# MCU.net
KiCad netlist of a schematic drawn in Altium Designer
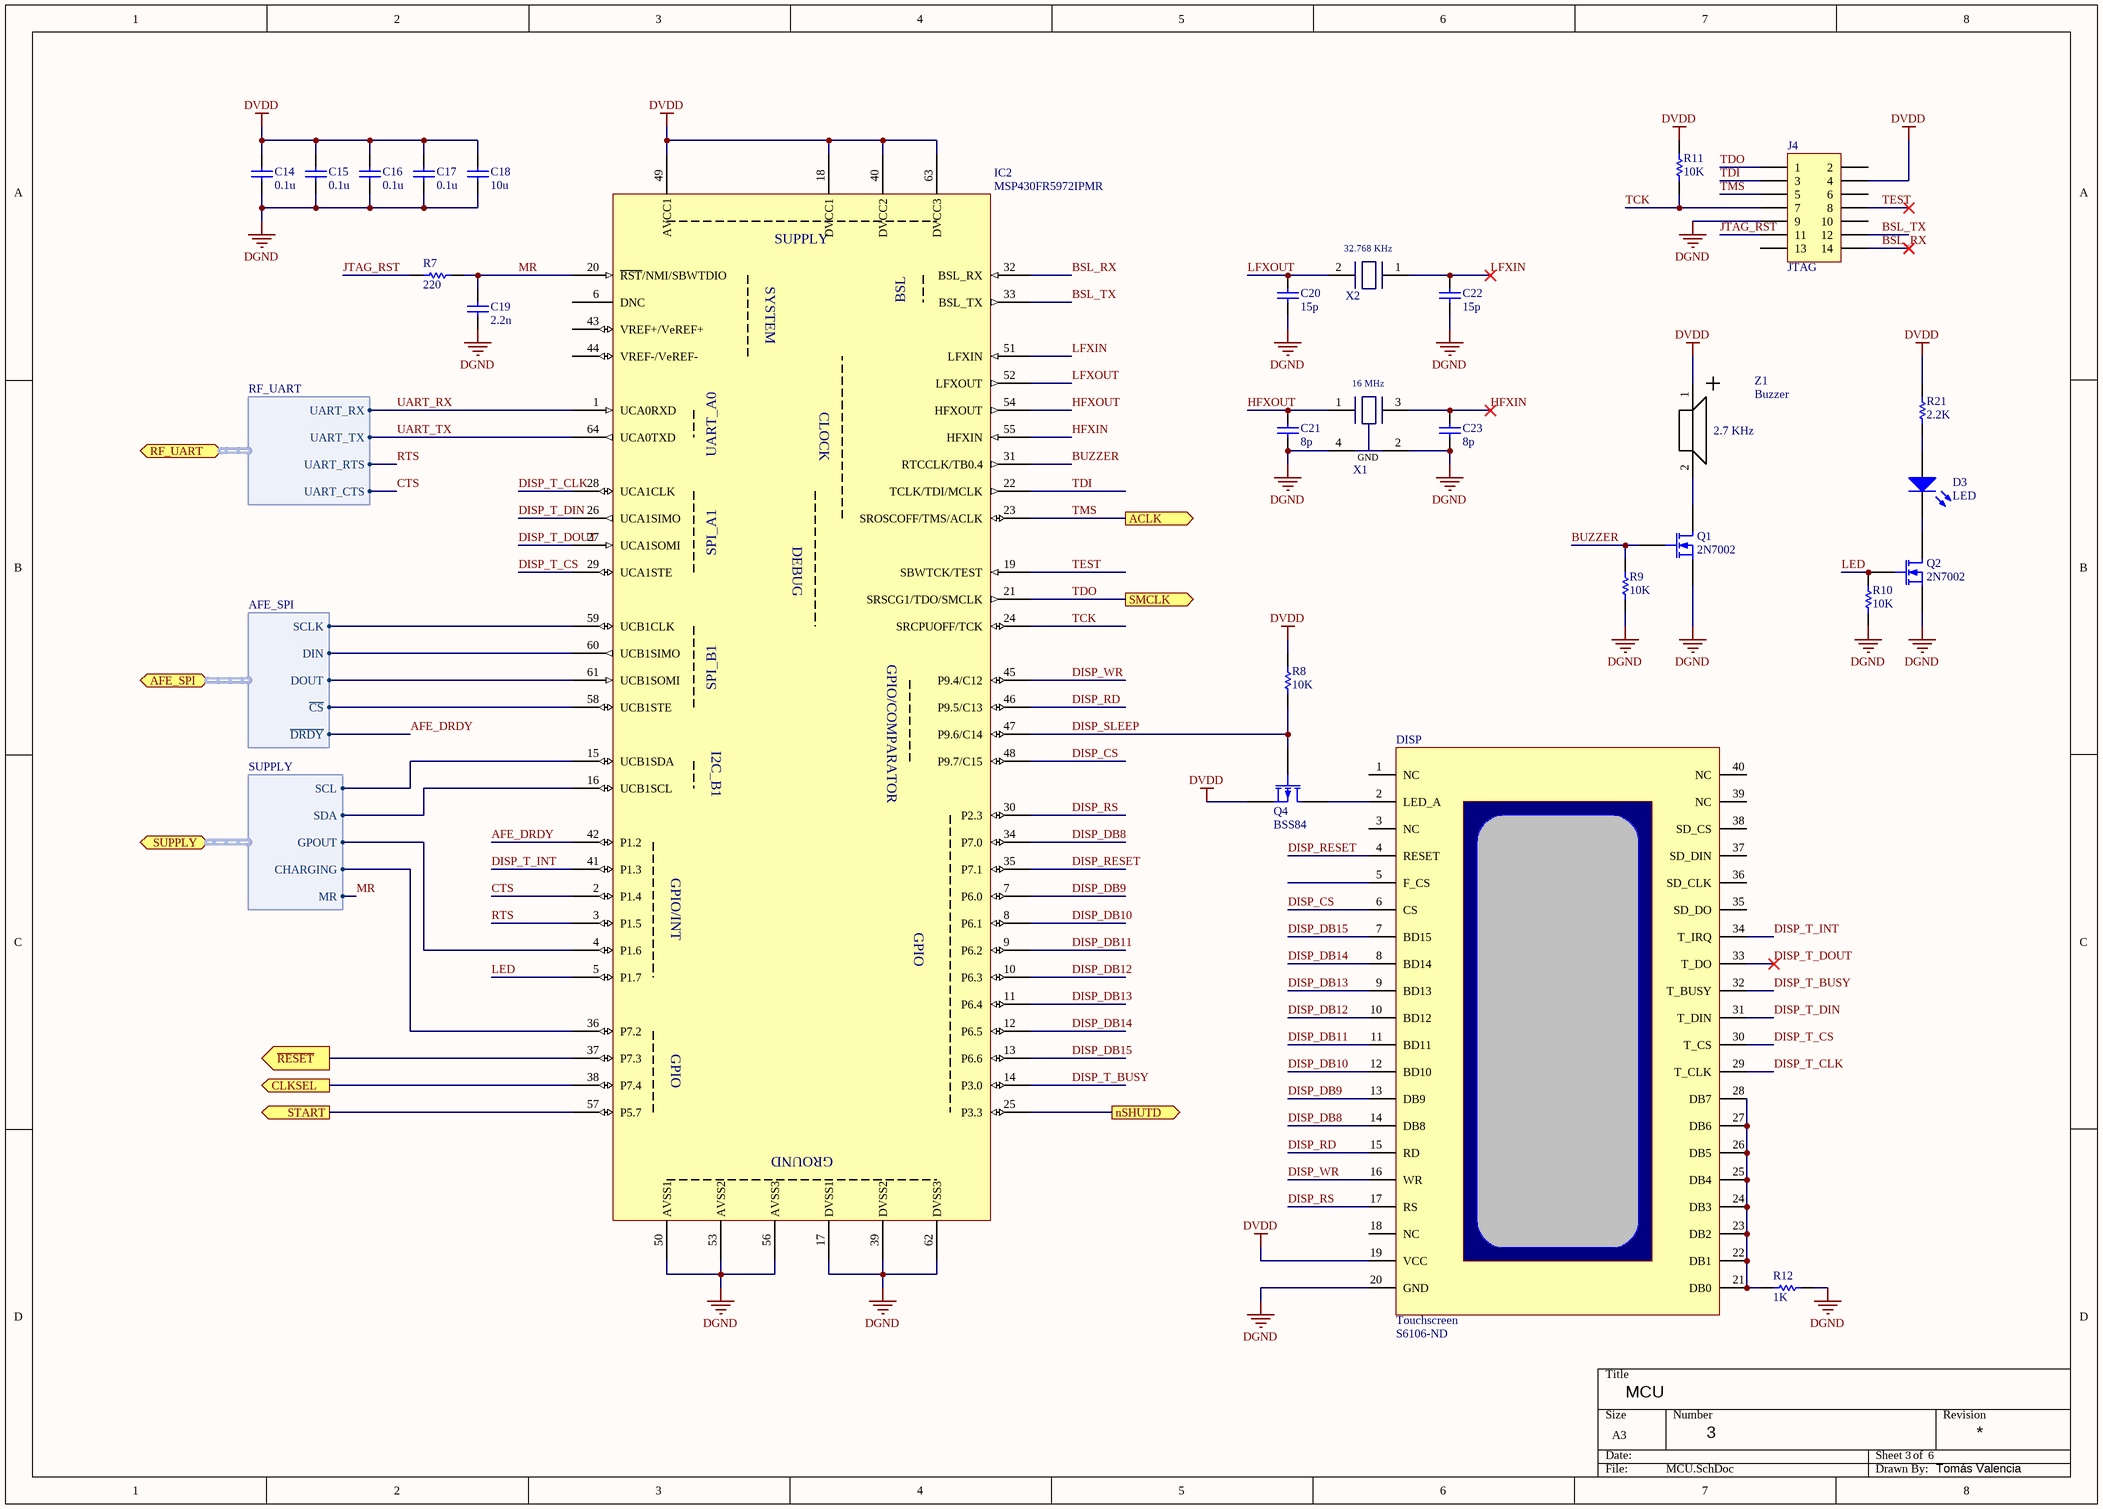
[diagram p0: MCU.SchDoc]

(export (version "E")
  (design (tool "Eeschema 10.0.6"))
  (components
    (comp (ref "C14")
      (value "0.1u")
      (footprint "C0603")
      (description "Capacitor")
      (libsource (lib "Common Devices") (part "Capacitor"))
    )
    (comp (ref "C15")
      (value "0.1u")
      (footprint "C0603")
      (description "Capacitor")
      (libsource (lib "Common Devices") (part "Capacitor"))
    )
    (comp (ref "C16")
      (value "0.1u")
      (footprint "C0603")
      (description "Capacitor")
      (libsource (lib "Common Devices") (part "Capacitor"))
    )
    (comp (ref "C17")
      (value "0.1u")
      (footprint "C0603")
      (description "Capacitor")
      (libsource (lib "Common Devices") (part "Capacitor"))
    )
    (comp (ref "C18")
      (value "10u")
      (footprint "C0603")
      (description "Capacitor")
      (libsource (lib "Common Devices") (part "Capacitor"))
    )
    (comp (ref "C19")
      (value "2.2n")
      (footprint "C0603")
      (description "Capacitor")
      (libsource (lib "Common Devices") (part "Capacitor"))
    )
    (comp (ref "C20")
      (value "15p")
      (footprint "C0603")
      (description "Capacitor")
      (libsource (lib "Common Devices") (part "Capacitor"))
    )
    (comp (ref "C21")
      (value "8p")
      (footprint "C0603")
      (description "Capacitor")
      (libsource (lib "Common Devices") (part "Capacitor"))
    )
    (comp (ref "C22")
      (value "15p")
      (footprint "C0603")
      (description "Capacitor")
      (libsource (lib "Common Devices") (part "Capacitor"))
    )
    (comp (ref "C23")
      (value "8p")
      (footprint "C0603")
      (description "Capacitor")
      (libsource (lib "Common Devices") (part "Capacitor"))
    )
    (comp (ref "D3") (value "LED") (footprint "LED3015M") (libsource (lib "Common Devices") (part "LED")))
    (comp (ref "DISP")
      (value "Touchscreen")
      (footprint "TSCREEN_CONN")
      (fields (field (name "SUPPLIER PART NUMBER 1") "S6106-ND"))
      (libsource (lib "Main Board") (part "Touchscreen"))
    )
    (comp (ref "IC2")
      (value "MSP430FR5972IPMR")
      (footprint "MSP430FR5972")
      (libsource (lib "Main Board") (part "MSP430FR5972IPMR"))
    )
    (comp (ref "J4")
      (value "JTAG")
      (footprint "JTAG 14 PINS")
      (description "JTAG 7X2 Pin Header 90º")
      (libsource (lib "Main Board") (part "JTAG 14 Pins"))
    )
    (comp (ref "Q1")
      (value "2N7002")
      (footprint "SOT65P210X110-3N")
      (description "Transistor, MOSFET, N-Channel, 60V, 300mA")
      (libsource (lib "Common Devices") (part "2N7002"))
    )
    (comp (ref "Q2")
      (value "2N7002")
      (footprint "SOT65P210X110-3N")
      (description "Transistor, MOSFET, N-Channel, 60V, 300mA")
      (libsource (lib "Common Devices") (part "2N7002"))
    )
    (comp (ref "Q4")
      (value "BSS84")
      (footprint "SOT65P210X110-3N")
      (description "Transistor, MOSFET, P-Channel, 60V, 300mA")
      (libsource (lib "Common Devices") (part "BSS84"))
    )
    (comp (ref "R7")
      (value "220")
      (footprint "R0603")
      (description "Resistor")
      (libsource (lib "Common Devices") (part "Resistor"))
    )
    (comp (ref "R8")
      (value "10K")
      (footprint "R0603")
      (description "Resistor")
      (libsource (lib "Common Devices") (part "Resistor"))
    )
    (comp (ref "R9")
      (value "10K")
      (footprint "R0603")
      (description "Resistor")
      (libsource (lib "Common Devices") (part "Resistor"))
    )
    (comp (ref "R10")
      (value "10K")
      (footprint "R0603")
      (description "Resistor")
      (libsource (lib "Common Devices") (part "Resistor"))
    )
    (comp (ref "R11")
      (value "10K")
      (footprint "R0603")
      (description "Resistor")
      (libsource (lib "Common Devices") (part "Resistor"))
    )
    (comp (ref "R12")
      (value "1K")
      (footprint "R0603")
      (description "Resistor")
      (libsource (lib "Common Devices") (part "Resistor"))
    )
    (comp (ref "R21")
      (value "2.2K")
      (footprint "R0603")
      (description "Resistor")
      (libsource (lib "Common Devices") (part "Resistor"))
    )
    (comp (ref "X1")
      (value "XTAL_16MHZ")
      (footprint "XTAL_16_MHz")
      (libsource (lib "Main Board") (part "XTAL_16_MHz"))
    )
    (comp (ref "X2")
      (value "XTAL_32768")
      (footprint "xtal_32768")
      (libsource (lib "Main Board") (part "XTAL_32768"))
    )
    (comp (ref "Z1")
      (value "Buzzer")
      (footprint "KSSG74B16")
      (description "Magnetic Buzzer 2.7 KHz")
      (libsource (lib "Main Board") (part "Buzzer"))
    )
  )
  (nets
    (net (code "4") (name "/AFE_DRDY") (class "Default")
      (node (ref "IC2") (pin "42") (pinfunction "P1.2_42") (pintype "bidirectional"))
    )
    (net (code "5") (name "/BSL_RX") (class "Default")
      (node (ref "IC2") (pin "32") (pinfunction "BSL_RX_32") (pintype "input"))
      (node (ref "J4") (pin "14") (pinfunction "14_14") (pintype "passive"))
    )
    (net (code "6") (name "/BSL_TX") (class "Default")
      (node (ref "IC2") (pin "33") (pinfunction "BSL_TX_33") (pintype "output"))
      (node (ref "J4") (pin "12") (pinfunction "12_12") (pintype "passive"))
    )
    (net (code "7") (name "/BUZZER") (class "Default")
      (node (ref "IC2") (pin "31") (pinfunction "RTCCLK/TB0.4_31") (pintype "output"))
      (node (ref "Q1") (pin "1") (pinfunction "G_1") (pintype "passive"))
      (node (ref "R9") (pin "2") (pinfunction "2_2") (pintype "passive"))
    )
    (net (code "8") (name "/CHARGING") (class "Default")
      (node (ref "IC2") (pin "36") (pinfunction "P7.2_36") (pintype "bidirectional"))
    )
    (net (code "9") (name "/CLKSEL") (class "Default")
      (node (ref "IC2") (pin "38") (pinfunction "P7.4_38") (pintype "bidirectional"))
    )
    (net (code "10") (name "/CTS") (class "Default")
      (node (ref "IC2") (pin "2") (pinfunction "P1.4_2") (pintype "bidirectional"))
    )
    (net (code "11") (name "/DIN") (class "Default")
      (node (ref "IC2") (pin "60") (pinfunction "UCB1SIMO_60") (pintype "output"))
    )
    (net (code "12") (name "/DISP_CS") (class "Default")
      (node (ref "DISP") (pin "6") (pinfunction "CS_6") (pintype "passive"))
      (node (ref "IC2") (pin "48") (pinfunction "P9.7/C15_48") (pintype "bidirectional"))
    )
    (net (code "13") (name "/DISP_DB8") (class "Default")
      (node (ref "DISP") (pin "14") (pinfunction "DB8_14") (pintype "passive"))
      (node (ref "IC2") (pin "34") (pinfunction "P7.0_34") (pintype "bidirectional"))
    )
    (net (code "14") (name "/DISP_DB9") (class "Default")
      (node (ref "DISP") (pin "13") (pinfunction "DB9_13") (pintype "passive"))
      (node (ref "IC2") (pin "7") (pinfunction "P6.0_7") (pintype "bidirectional"))
    )
    (net (code "15") (name "/DISP_DB10") (class "Default")
      (node (ref "DISP") (pin "12") (pinfunction "BD10_12") (pintype "passive"))
      (node (ref "IC2") (pin "8") (pinfunction "P6.1_8") (pintype "bidirectional"))
    )
    (net (code "16") (name "/DISP_DB11") (class "Default")
      (node (ref "DISP") (pin "11") (pinfunction "BD11_11") (pintype "passive"))
      (node (ref "IC2") (pin "9") (pinfunction "P6.2_9") (pintype "bidirectional"))
    )
    (net (code "17") (name "/DISP_DB12") (class "Default")
      (node (ref "DISP") (pin "10") (pinfunction "BD12_10") (pintype "passive"))
      (node (ref "IC2") (pin "10") (pinfunction "P6.3_10") (pintype "bidirectional"))
    )
    (net (code "18") (name "/DISP_DB13") (class "Default")
      (node (ref "DISP") (pin "9") (pinfunction "BD13_9") (pintype "passive"))
      (node (ref "IC2") (pin "11") (pinfunction "P6.4_11") (pintype "bidirectional"))
    )
    (net (code "19") (name "/DISP_DB14") (class "Default")
      (node (ref "DISP") (pin "8") (pinfunction "BD14_8") (pintype "passive"))
      (node (ref "IC2") (pin "12") (pinfunction "P6.5_12") (pintype "bidirectional"))
    )
    (net (code "20") (name "/DISP_DB15") (class "Default")
      (node (ref "DISP") (pin "7") (pinfunction "BD15_7") (pintype "passive"))
      (node (ref "IC2") (pin "13") (pinfunction "P6.6_13") (pintype "bidirectional"))
    )
    (net (code "21") (name "/DISP_RD") (class "Default")
      (node (ref "DISP") (pin "15") (pinfunction "RD_15") (pintype "passive"))
      (node (ref "IC2") (pin "46") (pinfunction "P9.5/C13_46") (pintype "bidirectional"))
    )
    (net (code "22") (name "/DISP_RESET") (class "Default")
      (node (ref "DISP") (pin "4") (pinfunction "RESET_4") (pintype "passive"))
      (node (ref "IC2") (pin "35") (pinfunction "P7.1_35") (pintype "bidirectional"))
    )
    (net (code "23") (name "/DISP_RS") (class "Default")
      (node (ref "DISP") (pin "17") (pinfunction "RS_17") (pintype "passive"))
      (node (ref "IC2") (pin "30") (pinfunction "P2.3_30") (pintype "bidirectional"))
    )
    (net (code "24") (name "/DISP_SLEEP") (class "Default")
      (node (ref "IC2") (pin "47") (pinfunction "P9.6/C14_47") (pintype "bidirectional"))
      (node (ref "Q4") (pin "1") (pinfunction "G_1") (pintype "passive"))
      (node (ref "R8") (pin "1") (pinfunction "1_1") (pintype "passive"))
    )
    (net (code "25") (name "/DISP_T_BUSY") (class "Default")
      (node (ref "DISP") (pin "32") (pinfunction "T_BUSY_32") (pintype "passive"))
      (node (ref "IC2") (pin "14") (pinfunction "P3.0_14") (pintype "bidirectional"))
    )
    (net (code "26") (name "/DISP_T_CLK") (class "Default")
      (node (ref "DISP") (pin "29") (pinfunction "T_CLK_29") (pintype "passive"))
      (node (ref "IC2") (pin "28") (pinfunction "UCA1CLK_28") (pintype "bidirectional"))
    )
    (net (code "27") (name "/DISP_T_CS") (class "Default")
      (node (ref "DISP") (pin "30") (pinfunction "T_CS_30") (pintype "passive"))
      (node (ref "IC2") (pin "29") (pinfunction "UCA1STE_29") (pintype "bidirectional"))
    )
    (net (code "28") (name "/DISP_T_DIN") (class "Default")
      (node (ref "DISP") (pin "31") (pinfunction "T_DIN_31") (pintype "passive"))
      (node (ref "IC2") (pin "26") (pinfunction "UCA1SIMO_26") (pintype "output"))
    )
    (net (code "29") (name "/DISP_T_DOUT") (class "Default")
      (node (ref "DISP") (pin "33") (pinfunction "T_DO_33") (pintype "passive"))
      (node (ref "IC2") (pin "27") (pinfunction "UCA1SOMI_27") (pintype "input"))
    )
    (net (code "30") (name "/DISP_T_INT") (class "Default")
      (node (ref "DISP") (pin "34") (pinfunction "T_IRQ_34") (pintype "passive"))
      (node (ref "IC2") (pin "41") (pinfunction "P1.3_41") (pintype "bidirectional"))
    )
    (net (code "31") (name "/DISP_WR") (class "Default")
      (node (ref "DISP") (pin "16") (pinfunction "WR_16") (pintype "passive"))
      (node (ref "IC2") (pin "45") (pinfunction "P9.4/C12_45") (pintype "bidirectional"))
    )
    (net (code "32") (name "/DOUT") (class "Default")
      (node (ref "IC2") (pin "61") (pinfunction "UCB1SOMI_61") (pintype "input"))
    )
    (net (code "33") (name "/GPOUT") (class "Default")
      (node (ref "IC2") (pin "4") (pinfunction "P1.6_4") (pintype "bidirectional"))
    )
    (net (code "34") (name "/HFXIN") (class "Default")
      (node (ref "C23") (pin "2") (pinfunction "2_2") (pintype "passive"))
      (node (ref "IC2") (pin "55") (pinfunction "HFXIN_55") (pintype "input"))
      (node (ref "X1") (pin "3") (pinfunction "IN_3") (pintype "passive"))
    )
    (net (code "35") (name "/HFXOUT") (class "Default")
      (node (ref "C21") (pin "2") (pinfunction "2_2") (pintype "passive"))
      (node (ref "IC2") (pin "54") (pinfunction "HFXOUT_54") (pintype "output"))
      (node (ref "X1") (pin "1") (pinfunction "OUT_1") (pintype "passive"))
    )
    (net (code "36") (name "/JTAG_RST") (class "Default")
      (node (ref "J4") (pin "11") (pinfunction "11_11") (pintype "passive"))
      (node (ref "R7") (pin "1") (pinfunction "1_1") (pintype "passive"))
    )
    (net (code "37") (name "/LED") (class "Default")
      (node (ref "IC2") (pin "5") (pinfunction "P1.7_5") (pintype "bidirectional"))
      (node (ref "Q2") (pin "1") (pinfunction "G_1") (pintype "passive"))
      (node (ref "R10") (pin "2") (pinfunction "2_2") (pintype "passive"))
    )
    (net (code "38") (name "/LFXIN") (class "Default")
      (node (ref "C22") (pin "1") (pinfunction "1_1") (pintype "passive"))
      (node (ref "IC2") (pin "51") (pinfunction "LFXIN_51") (pintype "input"))
      (node (ref "X2") (pin "1") (pinfunction "IN_1") (pintype "passive"))
    )
    (net (code "39") (name "/LFXOUT") (class "Default")
      (node (ref "C20") (pin "1") (pinfunction "1_1") (pintype "passive"))
      (node (ref "IC2") (pin "52") (pinfunction "LFXOUT_52") (pintype "output"))
      (node (ref "X2") (pin "2") (pinfunction "OUT_2") (pintype "passive"))
    )
    (net (code "40") (name "/MR") (class "Default")
      (node (ref "C19") (pin "2") (pinfunction "2_2") (pintype "passive"))
      (node (ref "IC2") (pin "20") (pinfunction "~{RST}/NMI/SBWTDIO_20") (pintype "input"))
      (node (ref "R7") (pin "2") (pinfunction "2_2") (pintype "passive"))
    )
    (net (code "41") (name "/RTS") (class "Default")
      (node (ref "IC2") (pin "3") (pinfunction "P1.5_3") (pintype "bidirectional"))
    )
    (net (code "42") (name "/SCL") (class "Default")
      (node (ref "IC2") (pin "15") (pinfunction "UCB1SDA_15") (pintype "bidirectional"))
    )
    (net (code "43") (name "/SCLK") (class "Default")
      (node (ref "IC2") (pin "59") (pinfunction "UCB1CLK_59") (pintype "bidirectional"))
    )
    (net (code "44") (name "/SDA") (class "Default")
      (node (ref "IC2") (pin "16") (pinfunction "UCB1SCL_16") (pintype "bidirectional"))
    )
    (net (code "45") (name "/START") (class "Default")
      (node (ref "IC2") (pin "57") (pinfunction "P5.7_57") (pintype "bidirectional"))
    )
    (net (code "46") (name "/TCK") (class "Default")
      (node (ref "IC2") (pin "24") (pinfunction "SRCPUOFF/TCK_24") (pintype "bidirectional"))
      (node (ref "J4") (pin "7") (pinfunction "7_7") (pintype "passive"))
      (node (ref "R11") (pin "1") (pinfunction "1_1") (pintype "passive"))
    )
    (net (code "47") (name "/TDI") (class "Default")
      (node (ref "IC2") (pin "22") (pinfunction "TCLK/TDI/MCLK_22") (pintype "output"))
      (node (ref "J4") (pin "3") (pinfunction "3_3") (pintype "passive"))
    )
    (net (code "48") (name "/TDO") (class "Default")
      (node (ref "IC2") (pin "21") (pinfunction "SRSCG1/TDO/SMCLK_21") (pintype "output"))
      (node (ref "J4") (pin "1") (pinfunction "1_1") (pintype "passive"))
    )
    (net (code "49") (name "/TEST") (class "Default")
      (node (ref "IC2") (pin "19") (pinfunction "SBWTCK/TEST_19") (pintype "input"))
      (node (ref "J4") (pin "8") (pinfunction "8_8") (pintype "passive"))
    )
    (net (code "50") (name "/TMS") (class "Default")
      (node (ref "IC2") (pin "23") (pinfunction "SROSCOFF/TMS/ACLK_23") (pintype "bidirectional"))
      (node (ref "J4") (pin "5") (pinfunction "5_5") (pintype "passive"))
    )
    (net (code "51") (name "/UART_RX") (class "Default")
      (node (ref "IC2") (pin "1") (pinfunction "UCA0RXD_1") (pintype "input"))
    )
    (net (code "52") (name "/UART_TX") (class "Default")
      (node (ref "IC2") (pin "64") (pinfunction "UCA0TXD_64") (pintype "output"))
    )
    (net (code "53") (name "/nSHUTD") (class "Default")
      (node (ref "IC2") (pin "25") (pinfunction "P3.3_25") (pintype "bidirectional"))
    )
    (net (code "57") (name "/~{CS}") (class "Default")
      (node (ref "IC2") (pin "58") (pinfunction "UCB1STE_58") (pintype "bidirectional"))
    )
    (net (code "58") (name "/~{RESET}") (class "Default")
      (node (ref "IC2") (pin "37") (pinfunction "P7.3_37") (pintype "bidirectional"))
    )
    (net (code "59") (name "DGND") (class "Default")
      (node (ref "C14") (pin "1") (pinfunction "1_1") (pintype "passive"))
      (node (ref "C15") (pin "1") (pinfunction "1_1") (pintype "passive"))
      (node (ref "C16") (pin "1") (pinfunction "1_1") (pintype "passive"))
      (node (ref "C17") (pin "1") (pinfunction "1_1") (pintype "passive"))
      (node (ref "C18") (pin "1") (pinfunction "1_1") (pintype "passive"))
      (node (ref "C19") (pin "1") (pinfunction "1_1") (pintype "passive"))
      (node (ref "C20") (pin "2") (pinfunction "2_2") (pintype "passive"))
      (node (ref "C21") (pin "1") (pinfunction "1_1") (pintype "passive"))
      (node (ref "C22") (pin "2") (pinfunction "2_2") (pintype "passive"))
      (node (ref "C23") (pin "1") (pinfunction "1_1") (pintype "passive"))
      (node (ref "DISP") (pin "20") (pinfunction "GND_20") (pintype "passive"))
      (node (ref "IC2") (pin "17") (pinfunction "DVSS1_17") (pintype "power_in"))
      (node (ref "IC2") (pin "39") (pinfunction "DVSS2_39") (pintype "power_in"))
      (node (ref "IC2") (pin "50") (pinfunction "AVSS1_50") (pintype "passive"))
      (node (ref "IC2") (pin "53") (pinfunction "AVSS2_53") (pintype "passive"))
      (node (ref "IC2") (pin "56") (pinfunction "AVSS3_56") (pintype "passive"))
      (node (ref "IC2") (pin "62") (pinfunction "DVSS3_62") (pintype "power_in"))
      (node (ref "J4") (pin "9") (pinfunction "9_9") (pintype "passive"))
      (node (ref "Q1") (pin "2") (pinfunction "S_2") (pintype "passive"))
      (node (ref "Q2") (pin "2") (pinfunction "S_2") (pintype "passive"))
      (node (ref "R10") (pin "1") (pinfunction "1_1") (pintype "passive"))
      (node (ref "R12") (pin "2") (pinfunction "2_2") (pintype "passive"))
      (node (ref "R9") (pin "1") (pinfunction "1_1") (pintype "passive"))
      (node (ref "X1") (pin "2") (pinfunction "GND_2") (pintype "passive"))
      (node (ref "X1") (pin "4") (pinfunction "GND_4") (pintype "passive"))
    )
    (net (code "60") (name "DVDD") (class "Default")
      (node (ref "C14") (pin "2") (pinfunction "2_2") (pintype "passive"))
      (node (ref "C15") (pin "2") (pinfunction "2_2") (pintype "passive"))
      (node (ref "C16") (pin "2") (pinfunction "2_2") (pintype "passive"))
      (node (ref "C17") (pin "2") (pinfunction "2_2") (pintype "passive"))
      (node (ref "C18") (pin "2") (pinfunction "2_2") (pintype "passive"))
      (node (ref "DISP") (pin "19") (pinfunction "VCC_19") (pintype "passive"))
      (node (ref "IC2") (pin "18") (pinfunction "DVCC1_18") (pintype "power_in"))
      (node (ref "IC2") (pin "40") (pinfunction "DVCC2_40") (pintype "power_in"))
      (node (ref "IC2") (pin "49") (pinfunction "AVCC1_49") (pintype "power_in"))
      (node (ref "IC2") (pin "63") (pinfunction "DVCC3_63") (pintype "power_in"))
      (node (ref "J4") (pin "4") (pinfunction "4_4") (pintype "passive"))
      (node (ref "Q4") (pin "2") (pinfunction "S_2") (pintype "passive"))
      (node (ref "R11") (pin "2") (pinfunction "2_2") (pintype "passive"))
      (node (ref "R21") (pin "2") (pinfunction "2_2") (pintype "passive"))
      (node (ref "R8") (pin "2") (pinfunction "2_2") (pintype "passive"))
      (node (ref "Z1") (pin "1") (pinfunction "+_1") (pintype "passive"))
    )
    (net (code "61") (name "Net-(D3-A)") (class "Default")
      (node (ref "D3") (pin "1") (pinfunction "A_1") (pintype "passive"))
      (node (ref "R21") (pin "1") (pinfunction "1_1") (pintype "passive"))
    )
    (net (code "62") (name "Net-(D3-K)") (class "Default")
      (node (ref "D3") (pin "2") (pinfunction "K_2") (pintype "passive"))
      (node (ref "Q2") (pin "3") (pinfunction "D_3") (pintype "passive"))
    )
    (net (code "63") (name "Net-(DISP-DB0)") (class "Default")
      (node (ref "DISP") (pin "21") (pinfunction "DB0_21") (pintype "passive"))
      (node (ref "DISP") (pin "22") (pinfunction "DB1_22") (pintype "passive"))
      (node (ref "DISP") (pin "23") (pinfunction "DB2_23") (pintype "passive"))
      (node (ref "DISP") (pin "24") (pinfunction "DB3_24") (pintype "passive"))
      (node (ref "DISP") (pin "25") (pinfunction "DB4_25") (pintype "passive"))
      (node (ref "DISP") (pin "26") (pinfunction "DB5_26") (pintype "passive"))
      (node (ref "DISP") (pin "27") (pinfunction "DB6_27") (pintype "passive"))
      (node (ref "DISP") (pin "28") (pinfunction "DB7_28") (pintype "passive"))
      (node (ref "R12") (pin "1") (pinfunction "1_1") (pintype "passive"))
    )
    (net (code "64") (name "Net-(DISP-LED_A)") (class "Default")
      (node (ref "DISP") (pin "2") (pinfunction "LED_A_2") (pintype "passive"))
      (node (ref "Q4") (pin "3") (pinfunction "D_3") (pintype "passive"))
    )
    (net (code "65") (name "Net-(Q1-D)") (class "Default")
      (node (ref "Q1") (pin "3") (pinfunction "D_3") (pintype "passive"))
      (node (ref "Z1") (pin "2") (pinfunction "-_2") (pintype "passive"))
    )
    (net (code "66") (name "unconnected-(DISP-F_CS-Pad5)") (class "Default")
      (node (ref "DISP") (pin "5") (pinfunction "F_CS_5") (pintype "passive"))
    )
    (net (code "67") (name "unconnected-(DISP-NC-Pad1)") (class "Default")
      (node (ref "DISP") (pin "1") (pinfunction "NC_1") (pintype "passive"))
    )
    (net (code "68") (name "unconnected-(DISP-NC-Pad3)") (class "Default")
      (node (ref "DISP") (pin "3") (pinfunction "NC_3") (pintype "passive"))
    )
    (net (code "69") (name "unconnected-(DISP-NC-Pad18)") (class "Default")
      (node (ref "DISP") (pin "18") (pinfunction "NC_18") (pintype "passive"))
    )
    (net (code "70") (name "unconnected-(DISP-NC-Pad39)") (class "Default")
      (node (ref "DISP") (pin "39") (pinfunction "NC_39") (pintype "passive"))
    )
    (net (code "71") (name "unconnected-(DISP-NC-Pad40)") (class "Default")
      (node (ref "DISP") (pin "40") (pinfunction "NC_40") (pintype "passive"))
    )
    (net (code "72") (name "unconnected-(DISP-SD_CLK-Pad36)") (class "Default")
      (node (ref "DISP") (pin "36") (pinfunction "SD_CLK_36") (pintype "passive"))
    )
    (net (code "73") (name "unconnected-(DISP-SD_CS-Pad38)") (class "Default")
      (node (ref "DISP") (pin "38") (pinfunction "SD_CS_38") (pintype "passive"))
    )
    (net (code "74") (name "unconnected-(DISP-SD_DIN-Pad37)") (class "Default")
      (node (ref "DISP") (pin "37") (pinfunction "SD_DIN_37") (pintype "passive"))
    )
    (net (code "75") (name "unconnected-(DISP-SD_DO-Pad35)") (class "Default")
      (node (ref "DISP") (pin "35") (pinfunction "SD_DO_35") (pintype "passive"))
    )
    (net (code "76") (name "unconnected-(IC2-DNC-Pad6)") (class "Default")
      (node (ref "IC2") (pin "6") (pinfunction "DNC_6") (pintype "tri_state"))
    )
    (net (code "77") (name "unconnected-(IC2-VREF+{slash}VeREF+-Pad43)") (class "Default")
      (node (ref "IC2") (pin "43") (pinfunction "VREF+/VeREF+_43") (pintype "bidirectional"))
    )
    (net (code "78") (name "unconnected-(IC2-VREF-{slash}VeREF--Pad44)") (class "Default")
      (node (ref "IC2") (pin "44") (pinfunction "VREF-/VeREF-_44") (pintype "bidirectional"))
    )
    (net (code "79") (name "unconnected-(J4-Pad2)") (class "Default")
      (node (ref "J4") (pin "2") (pinfunction "2_2") (pintype "passive"))
    )
    (net (code "80") (name "unconnected-(J4-Pad6)") (class "Default")
      (node (ref "J4") (pin "6") (pinfunction "6_6") (pintype "passive"))
    )
    (net (code "81") (name "unconnected-(J4-Pad10)") (class "Default")
      (node (ref "J4") (pin "10") (pinfunction "10_10") (pintype "passive"))
    )
    (net (code "82") (name "unconnected-(J4-Pad13)") (class "Default")
      (node (ref "J4") (pin "13") (pinfunction "13_13") (pintype "passive"))
    )
  )
)
